# smartmp3.net
KiCad netlist of a schematic drawn in EasyEDA Pro
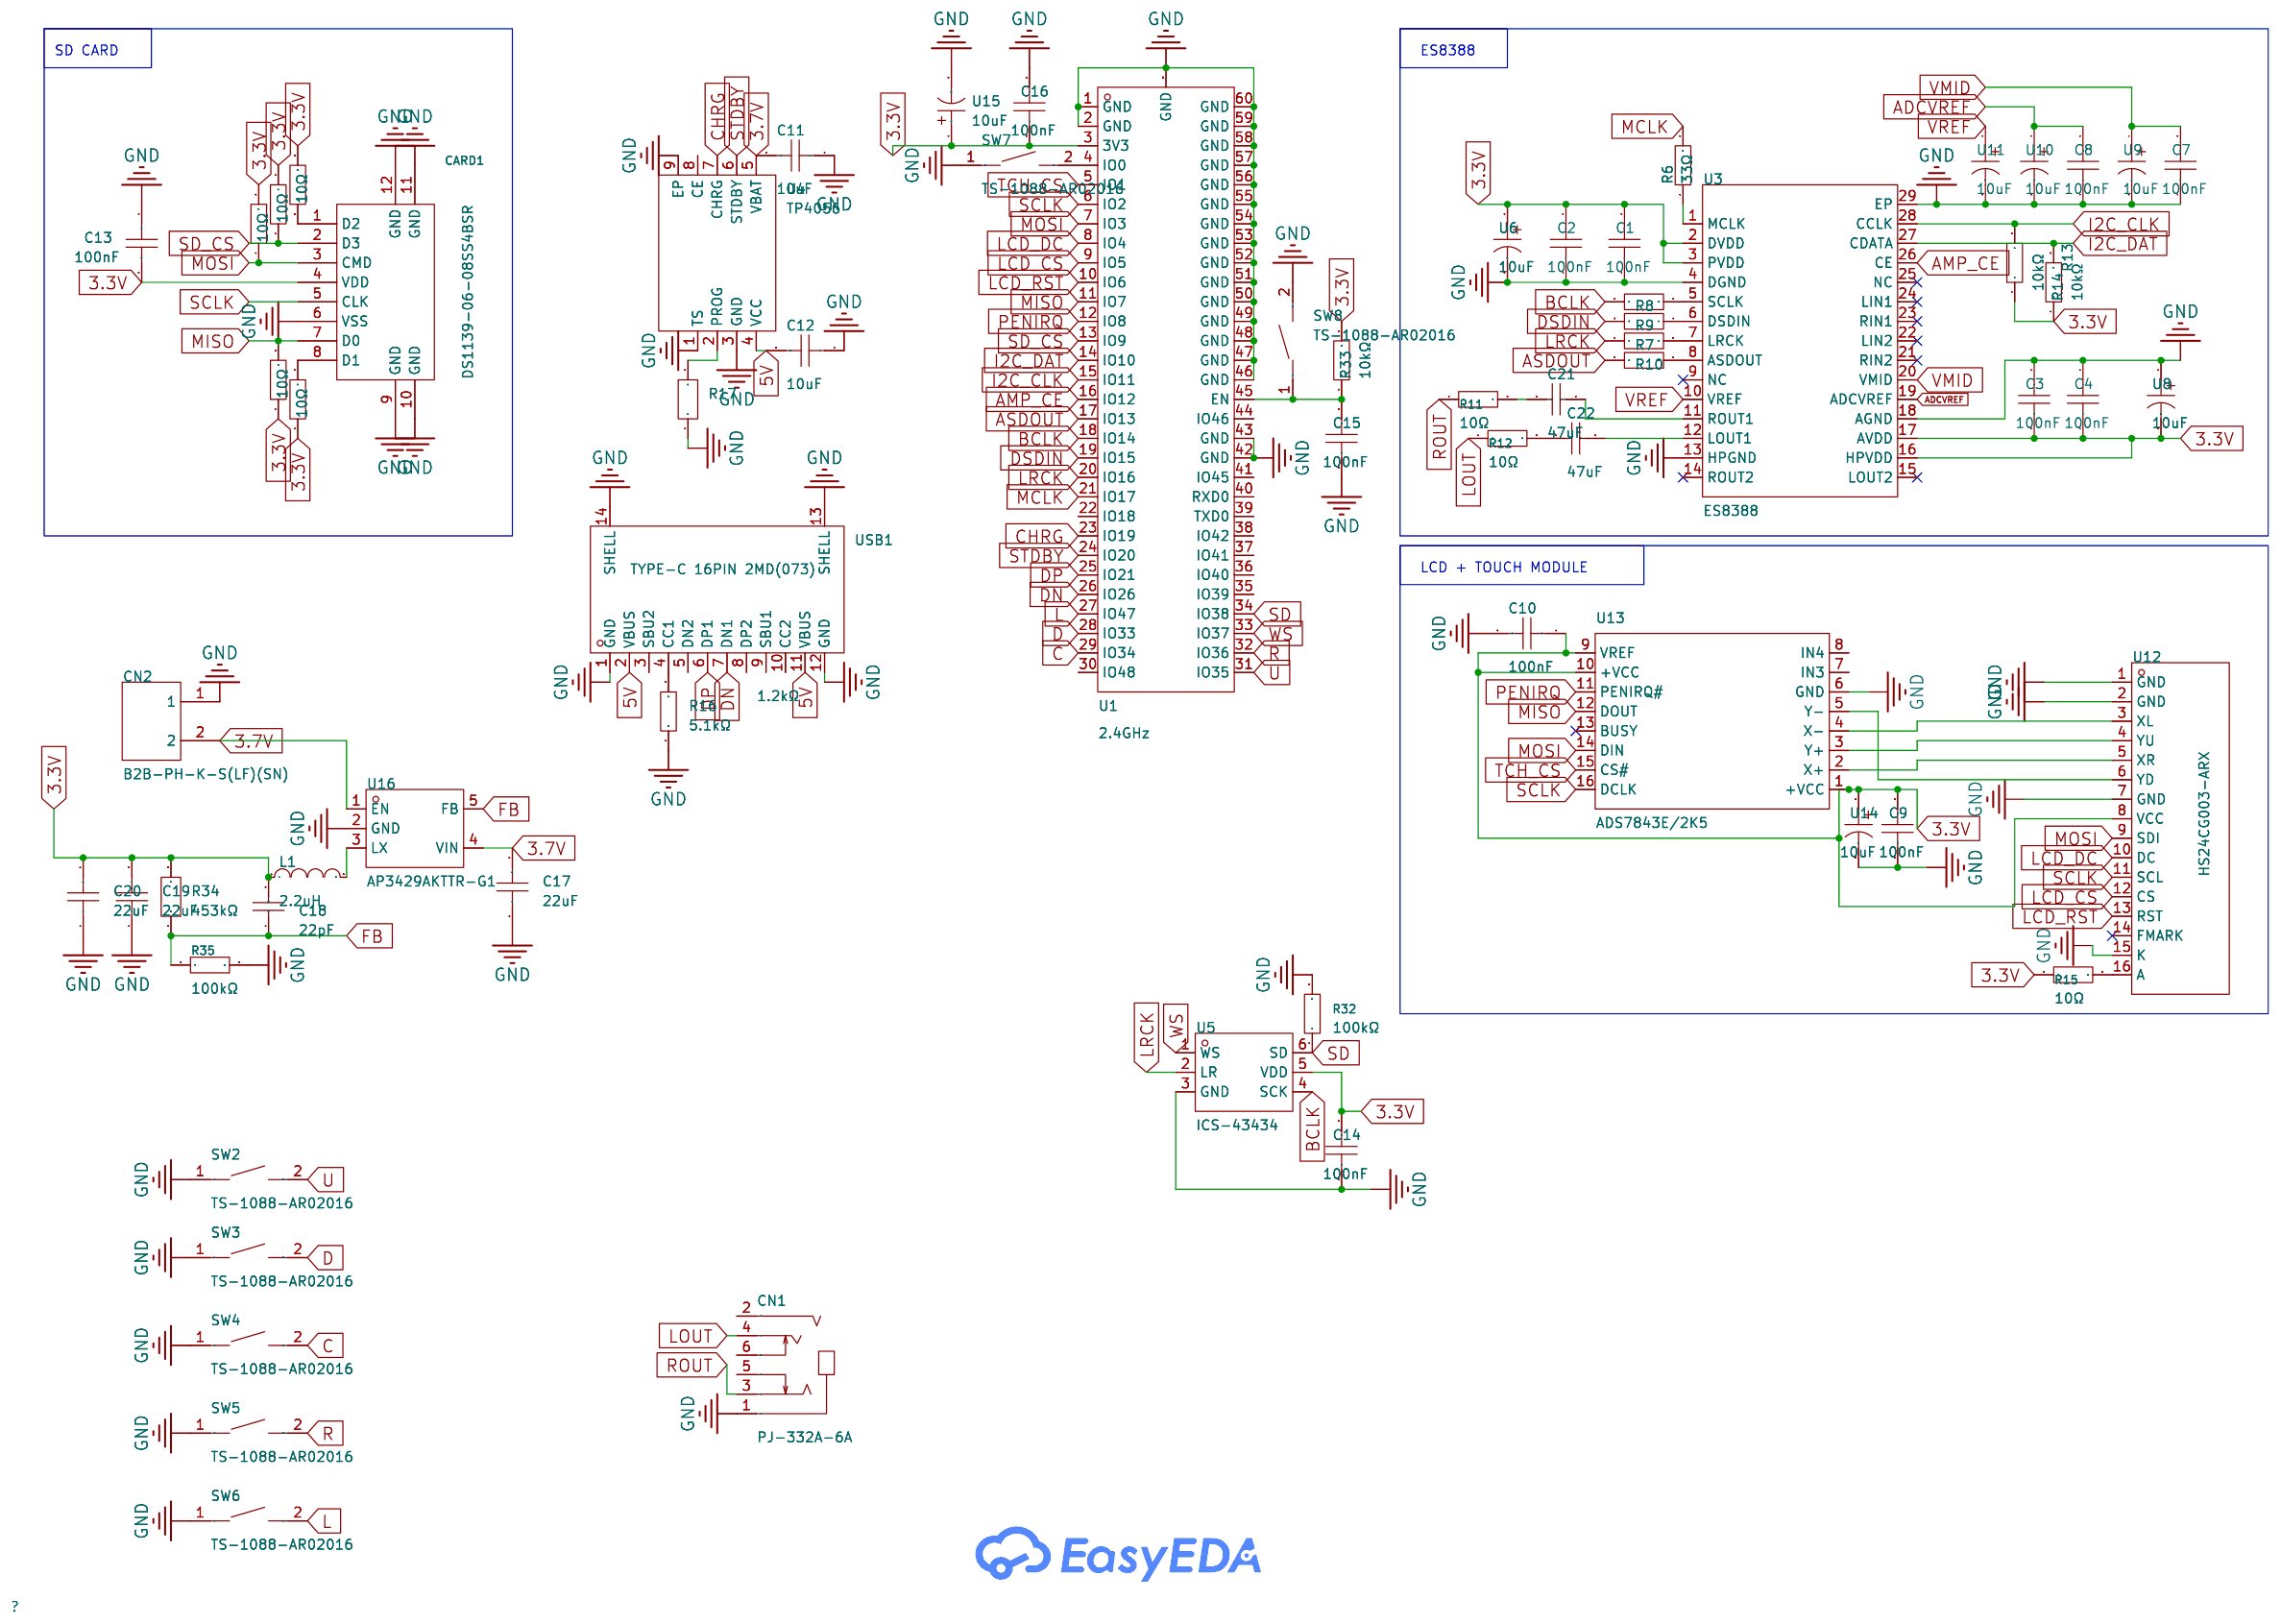
[diagram p0: schematic sheet]

(export (version "E")
  (design (tool "Eeschema 10.0.6"))
  (components
    (comp (ref "C1")
      (value "100nF")
      (footprint "easyedapro:C0402")
      (description "Capacitance:100nF Tolerance:±10% Tolerance:±10% Voltage Rating:16V Temperature Coefficient:-")
      (fields
        (field (name "Manufacturer Part") "CT41G-0402-2X1-16V-0.1μF-K(N)")
        (field (name "Manufacturer") "TORCH(火炬)")
      )
      (libsource (lib "easyedapro") (part "CT41G-0402-2X1-16V-0.1μF-K(N)"))
    )
    (comp (ref "C2")
      (value "100nF")
      (footprint "easyedapro:C0402")
      (description "Capacitance:100nF Tolerance:±10% Tolerance:±10% Voltage Rating:16V Temperature Coefficient:-")
      (fields
        (field (name "Manufacturer Part") "CT41G-0402-2X1-16V-0.1μF-K(N)")
        (field (name "Manufacturer") "TORCH(火炬)")
      )
      (libsource (lib "easyedapro") (part "CT41G-0402-2X1-16V-0.1μF-K(N)"))
    )
    (comp (ref "C3")
      (value "100nF")
      (footprint "easyedapro:C0402")
      (description "Capacitance:100nF Tolerance:±10% Tolerance:±10% Voltage Rating:16V Temperature Coefficient:-")
      (fields
        (field (name "Manufacturer Part") "CT41G-0402-2X1-16V-0.1μF-K(N)")
        (field (name "Manufacturer") "TORCH(火炬)")
      )
      (libsource (lib "easyedapro") (part "CT41G-0402-2X1-16V-0.1μF-K(N)"))
    )
    (comp (ref "C4")
      (value "100nF")
      (footprint "easyedapro:C0402")
      (description "Capacitance:100nF Tolerance:±10% Tolerance:±10% Voltage Rating:16V Temperature Coefficient:-")
      (fields
        (field (name "Manufacturer Part") "CT41G-0402-2X1-16V-0.1μF-K(N)")
        (field (name "Manufacturer") "TORCH(火炬)")
      )
      (libsource (lib "easyedapro") (part "CT41G-0402-2X1-16V-0.1μF-K(N)"))
    )
    (comp (ref "C7")
      (value "100nF")
      (footprint "easyedapro:C0402")
      (description "Capacitance:100nF Tolerance:±10% Tolerance:±10% Voltage Rating:16V Temperature Coefficient:-")
      (fields
        (field (name "Manufacturer Part") "CT41G-0402-2X1-16V-0.1μF-K(N)")
        (field (name "Manufacturer") "TORCH(火炬)")
      )
      (libsource (lib "easyedapro") (part "CT41G-0402-2X1-16V-0.1μF-K(N)"))
    )
    (comp (ref "C8")
      (value "100nF")
      (footprint "easyedapro:C0402")
      (description "Capacitance:100nF Tolerance:±10% Tolerance:±10% Voltage Rating:16V Temperature Coefficient:-")
      (fields
        (field (name "Manufacturer Part") "CT41G-0402-2X1-16V-0.1μF-K(N)")
        (field (name "Manufacturer") "TORCH(火炬)")
      )
      (libsource (lib "easyedapro") (part "CT41G-0402-2X1-16V-0.1μF-K(N)"))
    )
    (comp (ref "C9")
      (value "100nF")
      (footprint "easyedapro:C0402")
      (description "Capacitance:100nF Tolerance:±10% Tolerance:±10% Voltage Rating:16V Temperature Coefficient:-")
      (fields
        (field (name "Manufacturer Part") "CT41G-0402-2X1-16V-0.1μF-K(N)")
        (field (name "Manufacturer") "TORCH(火炬)")
      )
      (libsource (lib "easyedapro") (part "CT41G-0402-2X1-16V-0.1μF-K(N)"))
    )
    (comp (ref "C10")
      (value "100nF")
      (footprint "easyedapro:C0402")
      (description "Capacitance:100nF Tolerance:±10% Tolerance:±10% Voltage Rating:16V Temperature Coefficient:-")
      (fields
        (field (name "Manufacturer Part") "CT41G-0402-2X1-16V-0.1μF-K(N)")
        (field (name "Manufacturer") "TORCH(火炬)")
      )
      (libsource (lib "easyedapro") (part "CT41G-0402-2X1-16V-0.1μF-K(N)"))
    )
    (comp (ref "C11")
      (value "10uF")
      (footprint "easyedapro:C0805")
      (description "Capacitance:10uF Tolerance:±10% Tolerance:±10% Voltage Rating:25V Temperature Coefficient:X5R")
      (fields
        (field (name "Manufacturer Part") "CL21A106KAYNNNE")
        (field (name "Manufacturer") "SAMSUNG(三星)")
      )
      (libsource (lib "easyedapro") (part "CL21A106KAYNNNE"))
    )
    (comp (ref "C12")
      (value "10uF")
      (footprint "easyedapro:C0805")
      (description "Capacitance:10uF Tolerance:±10% Tolerance:±10% Voltage Rating:25V Temperature Coefficient:X5R")
      (fields
        (field (name "Manufacturer Part") "CL21A106KAYNNNE")
        (field (name "Manufacturer") "SAMSUNG(三星)")
      )
      (libsource (lib "easyedapro") (part "CL21A106KAYNNNE"))
    )
    (comp (ref "C13")
      (value "100nF")
      (footprint "easyedapro:C0402")
      (description "Capacitance:100nF Tolerance:±10% Tolerance:±10% Voltage Rating:16V Temperature Coefficient:-")
      (fields
        (field (name "Manufacturer Part") "CT41G-0402-2X1-16V-0.1μF-K(N)")
        (field (name "Manufacturer") "TORCH(火炬)")
      )
      (libsource (lib "easyedapro") (part "CT41G-0402-2X1-16V-0.1μF-K(N)"))
    )
    (comp (ref "C14")
      (value "100nF")
      (footprint "easyedapro:C0402")
      (description "Capacitance:100nF Tolerance:±10% Tolerance:±10% Voltage Rating:16V Temperature Coefficient:-")
      (fields
        (field (name "Manufacturer Part") "CT41G-0402-2X1-16V-0.1μF-K(N)")
        (field (name "Manufacturer") "TORCH(火炬)")
      )
      (libsource (lib "easyedapro") (part "CT41G-0402-2X1-16V-0.1μF-K(N)"))
    )
    (comp (ref "C15")
      (value "100nF")
      (footprint "easyedapro:C0402")
      (description "Capacitance:100nF Tolerance:±10% Tolerance:±10% Voltage Rating:16V Temperature Coefficient:-")
      (fields
        (field (name "Manufacturer Part") "CT41G-0402-2X1-16V-0.1μF-K(N)")
        (field (name "Manufacturer") "TORCH(火炬)")
      )
      (libsource (lib "easyedapro") (part "CT41G-0402-2X1-16V-0.1μF-K(N)"))
    )
    (comp (ref "C16")
      (value "100nF")
      (footprint "easyedapro:C0402")
      (description "Capacitance:100nF Tolerance:±10% Tolerance:±10% Voltage Rating:16V Temperature Coefficient:-")
      (fields
        (field (name "Manufacturer Part") "CT41G-0402-2X1-16V-0.1μF-K(N)")
        (field (name "Manufacturer") "TORCH(火炬)")
      )
      (libsource (lib "easyedapro") (part "CT41G-0402-2X1-16V-0.1μF-K(N)"))
    )
    (comp (ref "C17")
      (value "22uF")
      (footprint "easyedapro:C0805")
      (description "Capacitance:22uF Tolerance:±20% Tolerance:±20% Voltage Rating:25V Temperature Coefficient:X5R")
      (fields
        (field (name "Manufacturer Part") "CL21A226MAYNNNE")
        (field (name "Manufacturer") "SAMSUNG(三星)")
      )
      (libsource (lib "easyedapro") (part "CL21A226MAYNNNE"))
    )
    (comp (ref "C18")
      (value "22pF")
      (footprint "easyedapro:C0603")
      (description "Capacitance:22pF Tolerance:±5% Tolerance:±5% Voltage Rating:50V Temperature Coefficient:C0G")
      (fields
        (field (name "Manufacturer Part") "CL10C220JB8NNNC")
        (field (name "Manufacturer") "SAMSUNG(三星)")
      )
      (libsource (lib "easyedapro") (part "CL10C220JB8NNNC"))
    )
    (comp (ref "C19")
      (value "22uF")
      (footprint "easyedapro:C0805")
      (description "Capacitance:22uF Tolerance:±20% Tolerance:±20% Voltage Rating:25V Temperature Coefficient:X5R")
      (fields
        (field (name "Manufacturer Part") "CL21A226MAYNNNE")
        (field (name "Manufacturer") "SAMSUNG(三星)")
      )
      (libsource (lib "easyedapro") (part "CL21A226MAYNNNE"))
    )
    (comp (ref "C20")
      (value "22uF")
      (footprint "easyedapro:C0805")
      (description "Capacitance:22uF Tolerance:±20% Tolerance:±20% Voltage Rating:25V Temperature Coefficient:X5R")
      (fields
        (field (name "Manufacturer Part") "CL21A226MAYNNNE")
        (field (name "Manufacturer") "SAMSUNG(三星)")
      )
      (libsource (lib "easyedapro") (part "CL21A226MAYNNNE"))
    )
    (comp (ref "C21")
      (value "47uF")
      (footprint "easyedapro:C0805")
      (description "Capacitance:47uF Tolerance:±20% Tolerance:±20% Voltage Rating:6.3V Temperature Coefficient:X5R")
      (fields
        (field (name "Manufacturer Part") "CL21A476MQYNNNE")
        (field (name "Manufacturer") "SAMSUNG(三星)")
      )
      (libsource (lib "easyedapro") (part "CL21A476MQYNNNE"))
    )
    (comp (ref "C22")
      (value "47uF")
      (footprint "easyedapro:C0805")
      (description "Capacitance:47uF Tolerance:±20% Tolerance:±20% Voltage Rating:6.3V Temperature Coefficient:X5R")
      (fields
        (field (name "Manufacturer Part") "CL21A476MQYNNNE")
        (field (name "Manufacturer") "SAMSUNG(三星)")
      )
      (libsource (lib "easyedapro") (part "CL21A476MQYNNNE"))
    )
    (comp (ref "CARD1")
      (value "DS1139-06-08SS4BSR")
      (footprint "easyedapro:TF-SMD_DS1139-06-08SS4BSR")
      (fields (field (name "Manufacturer") "CONNFLY"))
      (libsource (lib "easyedapro") (part "DS1139-06-08SS4BSR"))
    )
    (comp (ref "CN1")
      (value "PJ-332A-6A")
      (footprint "easyedapro:AUDIO-SMD_PJ-332A-6A")
      (fields (field (name "Manufacturer") "韩国韩荣"))
      (libsource (lib "easyedapro") (part "PJ-332A-6A"))
    )
    (comp (ref "CN2")
      (value "B2B-PH-K-S(LF)(SN)")
      (footprint "easyedapro:CONN-TH_B2B-PH-K-S")
      (fields (field (name "Manufacturer") "JST"))
      (libsource (lib "easyedapro") (part "B2B-PH-K-S(LF)(SN)"))
    )
    (comp (ref "L1")
      (value "2.2uH")
      (footprint "easyedapro:L1008")
      (fields (field (name "Manufacturer Part") "LQM2HPN2R2MG0L") (field (name "Manufacturer") "muRata(村田)"))
      (libsource (lib "easyedapro") (part "LQM2HPN2R2MG0L"))
    )
    (comp (ref "R6")
      (value "33Ω")
      (footprint "easyedapro:R0402")
      (fields (field (name "Manufacturer Part") "RC0402FR-0733RL") (field (name "Manufacturer") "YAGEO(国巨)"))
      (libsource (lib "easyedapro") (part "RC0402FR-0733RL"))
    )
    (comp (ref "R7")
      (value "33Ω")
      (footprint "easyedapro:R0402")
      (fields (field (name "Manufacturer Part") "RC0402FR-0733RL") (field (name "Manufacturer") "YAGEO(国巨)"))
      (libsource (lib "easyedapro") (part "RC0402FR-0733RL"))
    )
    (comp (ref "R8")
      (value "33Ω")
      (footprint "easyedapro:R0402")
      (fields (field (name "Manufacturer Part") "RC0402FR-0733RL") (field (name "Manufacturer") "YAGEO(国巨)"))
      (libsource (lib "easyedapro") (part "RC0402FR-0733RL"))
    )
    (comp (ref "R9")
      (value "33Ω")
      (footprint "easyedapro:R0402")
      (fields (field (name "Manufacturer Part") "RC0402FR-0733RL") (field (name "Manufacturer") "YAGEO(国巨)"))
      (libsource (lib "easyedapro") (part "RC0402FR-0733RL"))
    )
    (comp (ref "R10")
      (value "33Ω")
      (footprint "easyedapro:R0402")
      (fields (field (name "Manufacturer Part") "RC0402FR-0733RL") (field (name "Manufacturer") "YAGEO(国巨)"))
      (libsource (lib "easyedapro") (part "RC0402FR-0733RL"))
    )
    (comp (ref "R11")
      (value "10Ω")
      (footprint "easyedapro:R0805_NEW")
      (fields
        (field (name "Manufacturer Part") "0805W8F100JT5E")
        (field (name "Manufacturer") "UNI-ROYAL(厚声)")
      )
      (libsource (lib "easyedapro") (part "0805W8F100JT5E"))
    )
    (comp (ref "R12")
      (value "10Ω")
      (footprint "easyedapro:R0805_NEW")
      (fields
        (field (name "Manufacturer Part") "0805W8F100JT5E")
        (field (name "Manufacturer") "UNI-ROYAL(厚声)")
      )
      (libsource (lib "easyedapro") (part "0805W8F100JT5E"))
    )
    (comp (ref "R13")
      (value "10kΩ")
      (footprint "easyedapro:R0603")
      (fields (field (name "Manufacturer Part") "RC0603FR-0710KL") (field (name "Manufacturer") "YAGEO(国巨)"))
      (libsource (lib "easyedapro") (part "RC0603FR-0710KL"))
    )
    (comp (ref "R14")
      (value "10kΩ")
      (footprint "easyedapro:R0603")
      (fields (field (name "Manufacturer Part") "RC0603FR-0710KL") (field (name "Manufacturer") "YAGEO(国巨)"))
      (libsource (lib "easyedapro") (part "RC0603FR-0710KL"))
    )
    (comp (ref "R15")
      (value "10Ω")
      (footprint "easyedapro:R0805_NEW")
      (fields
        (field (name "Manufacturer Part") "0805W8F100JT5E")
        (field (name "Manufacturer") "UNI-ROYAL(厚声)")
      )
      (libsource (lib "easyedapro") (part "0805W8F100JT5E"))
    )
    (comp (ref "R16")
      (value "5.1kΩ")
      (footprint "easyedapro:R0603")
      (fields (field (name "Manufacturer Part") "RC0603FR-075K1L") (field (name "Manufacturer") "YAGEO(国巨)"))
      (libsource (lib "easyedapro") (part "RC0603FR-075K1L"))
    )
    (comp (ref "R17")
      (value "1.2kΩ")
      (footprint "easyedapro:R1206")
      (fields (field (name "Manufacturer Part") "FRC1206J122 TS") (field (name "Manufacturer") "FOJAN(富捷)"))
      (libsource (lib "easyedapro") (part "FRC1206J122 TS"))
    )
    (comp (ref "R18")
      (value "10Ω")
      (footprint "easyedapro:R0805_NEW")
      (fields
        (field (name "Manufacturer Part") "0805W8F100JT5E")
        (field (name "Manufacturer") "UNI-ROYAL(厚声)")
      )
      (libsource (lib "easyedapro") (part "0805W8F100JT5E"))
    )
    (comp (ref "R19")
      (value "10Ω")
      (footprint "easyedapro:R0805_NEW")
      (fields
        (field (name "Manufacturer Part") "0805W8F100JT5E")
        (field (name "Manufacturer") "UNI-ROYAL(厚声)")
      )
      (libsource (lib "easyedapro") (part "0805W8F100JT5E"))
    )
    (comp (ref "R20")
      (value "10Ω")
      (footprint "easyedapro:R0805_NEW")
      (fields
        (field (name "Manufacturer Part") "0805W8F100JT5E")
        (field (name "Manufacturer") "UNI-ROYAL(厚声)")
      )
      (libsource (lib "easyedapro") (part "0805W8F100JT5E"))
    )
    (comp (ref "R22")
      (value "10Ω")
      (footprint "easyedapro:R0805_NEW")
      (fields
        (field (name "Manufacturer Part") "0805W8F100JT5E")
        (field (name "Manufacturer") "UNI-ROYAL(厚声)")
      )
      (libsource (lib "easyedapro") (part "0805W8F100JT5E"))
    )
    (comp (ref "R23")
      (value "10Ω")
      (footprint "easyedapro:R0805_NEW")
      (fields
        (field (name "Manufacturer Part") "0805W8F100JT5E")
        (field (name "Manufacturer") "UNI-ROYAL(厚声)")
      )
      (libsource (lib "easyedapro") (part "0805W8F100JT5E"))
    )
    (comp (ref "R32")
      (value "100kΩ")
      (footprint "easyedapro:R0603")
      (fields (field (name "Manufacturer Part") "RC0603FR-07100KL") (field (name "Manufacturer") "YAGEO(国巨)"))
      (libsource (lib "easyedapro") (part "RC0603FR-07100KL"))
    )
    (comp (ref "R33")
      (value "10kΩ")
      (footprint "easyedapro:R0603")
      (fields (field (name "Manufacturer Part") "RC0603FR-0710KL") (field (name "Manufacturer") "YAGEO(国巨)"))
      (libsource (lib "easyedapro") (part "RC0603FR-0710KL"))
    )
    (comp (ref "R34")
      (value "453kΩ")
      (footprint "easyedapro:R0603")
      (fields (field (name "Manufacturer Part") "FRC0603F4533TS") (field (name "Manufacturer") "FOJAN(富捷)"))
      (libsource (lib "easyedapro") (part "FRC0603F4533TS"))
    )
    (comp (ref "R35")
      (value "100kΩ")
      (footprint "easyedapro:R0603")
      (fields (field (name "Manufacturer Part") "RC0603FR-07100KL") (field (name "Manufacturer") "YAGEO(国巨)"))
      (libsource (lib "easyedapro") (part "RC0603FR-07100KL"))
    )
    (comp (ref "SW2")
      (value "TS-1088-AR02016")
      (footprint "easyedapro:SW-SMD_L3.9-W3.0-P4.45")
      (fields (field (name "Manufacturer") "XUNPU(讯普)"))
      (libsource (lib "easyedapro") (part "TS-1088-AR02016"))
    )
    (comp (ref "SW3")
      (value "TS-1088-AR02016")
      (footprint "easyedapro:SW-SMD_L3.9-W3.0-P4.45")
      (fields (field (name "Manufacturer") "XUNPU(讯普)"))
      (libsource (lib "easyedapro") (part "TS-1088-AR02016"))
    )
    (comp (ref "SW4")
      (value "TS-1088-AR02016")
      (footprint "easyedapro:SW-SMD_L3.9-W3.0-P4.45")
      (fields (field (name "Manufacturer") "XUNPU(讯普)"))
      (libsource (lib "easyedapro") (part "TS-1088-AR02016"))
    )
    (comp (ref "SW5")
      (value "TS-1088-AR02016")
      (footprint "easyedapro:SW-SMD_L3.9-W3.0-P4.45")
      (fields (field (name "Manufacturer") "XUNPU(讯普)"))
      (libsource (lib "easyedapro") (part "TS-1088-AR02016"))
    )
    (comp (ref "SW6")
      (value "TS-1088-AR02016")
      (footprint "easyedapro:SW-SMD_L3.9-W3.0-P4.45")
      (fields (field (name "Manufacturer") "XUNPU(讯普)"))
      (libsource (lib "easyedapro") (part "TS-1088-AR02016"))
    )
    (comp (ref "SW7")
      (value "TS-1088-AR02016")
      (footprint "easyedapro:SW-SMD_L3.9-W3.0-P4.45")
      (fields (field (name "Manufacturer") "XUNPU(讯普)"))
      (libsource (lib "easyedapro") (part "TS-1088-AR02016"))
    )
    (comp (ref "SW8")
      (value "TS-1088-AR02016")
      (footprint "easyedapro:SW-SMD_L3.9-W3.0-P4.45")
      (fields (field (name "Manufacturer") "XUNPU(讯普)"))
      (libsource (lib "easyedapro") (part "TS-1088-AR02016"))
    )
    (comp (ref "U1")
      (value "2.4GHz")
      (footprint "easyedapro:BULETM-SMD_ESP32-S3-MINI-1-N8")
      (fields
        (field (name "Manufacturer Part") "ESP32-S3-MINI-1-N8")
        (field (name "Manufacturer") "ESPRESSIF(乐鑫)")
      )
      (libsource (lib "easyedapro") (part "ESP32-S3-MINI-1-N8"))
    )
    (comp (ref "U3")
      (value "ES8388")
      (footprint "easyedapro:QFN-28_L4.0-W4.0-P0.45-BL-EP")
      (description "Voltage - Supply:1.7V~3.6V Voltage - Supply:1.7V~3.6V Interface Type:SPI；I2C")
      (fields (field (name "Manufacturer") "Everest-semi(顺芯)"))
      (libsource (lib "easyedapro") (part "ES8388"))
    )
    (comp (ref "U4")
      (value "TP4056")
      (footprint "easyedapro:ESOP-8_L4.9-W3.9-P1.27-LS6.0-BL-EP")
      (fields (field (name "Manufacturer") "JSMSEMI(杰盛微)"))
      (libsource (lib "easyedapro") (part "TP4056_C22470410"))
    )
    (comp (ref "U5")
      (value "ICS-43434")
      (footprint "easyedapro:MIC-SMD_6P-L3.5-W2.7-P0.90-BL")
      (fields (field (name "Manufacturer") "TDK InvenSense(应美盛)"))
      (libsource (lib "easyedapro") (part "ICS-43434_C5656610"))
    )
    (comp (ref "U6")
      (value "10uF")
      (footprint "easyedapro:CAP-SMD_BD4.0-L4.3-W4.3-LS5.0-FD")
      (fields (field (name "Manufacturer Part") "RST10UF35V015") (field (name "Manufacturer") "KNSCHA(科尼盛)"))
      (libsource (lib "easyedapro") (part "RST10UF35V015"))
    )
    (comp (ref "U8")
      (value "10uF")
      (footprint "easyedapro:CAP-SMD_BD4.0-L4.3-W4.3-LS5.0-FD")
      (fields (field (name "Manufacturer Part") "RST10UF35V015") (field (name "Manufacturer") "KNSCHA(科尼盛)"))
      (libsource (lib "easyedapro") (part "RST10UF35V015"))
    )
    (comp (ref "U9")
      (value "10uF")
      (footprint "easyedapro:CAP-SMD_BD4.0-L4.3-W4.3-LS5.0-FD")
      (fields (field (name "Manufacturer Part") "RST10UF35V015") (field (name "Manufacturer") "KNSCHA(科尼盛)"))
      (libsource (lib "easyedapro") (part "RST10UF35V015"))
    )
    (comp (ref "U10")
      (value "10uF")
      (footprint "easyedapro:CAP-SMD_BD4.0-L4.3-W4.3-LS5.0-FD")
      (fields (field (name "Manufacturer Part") "RST10UF35V015") (field (name "Manufacturer") "KNSCHA(科尼盛)"))
      (libsource (lib "easyedapro") (part "RST10UF35V015"))
    )
    (comp (ref "U11")
      (value "10uF")
      (footprint "easyedapro:CAP-SMD_BD4.0-L4.3-W4.3-LS5.0-FD")
      (fields (field (name "Manufacturer Part") "RST10UF35V015") (field (name "Manufacturer") "KNSCHA(科尼盛)"))
      (libsource (lib "easyedapro") (part "RST10UF35V015"))
    )
    (comp (ref "U12")
      (value "HS24CG003-ARX")
      (footprint "easyedapro:LCD-SMD_HS24CG003-ARX")
      (fields (field (name "Manufacturer") "HS(汉昇)"))
      (libsource (lib "easyedapro") (part "HS24CG003-ARX"))
    )
    (comp (ref "U13")
      (value "ADS7843E/2K5")
      (footprint "easyedapro:SSOP-16_L4.9-W3.9-P0.64-LS6.0-BL-1")
      (fields (field (name "Manufacturer") "TI(德州仪器)"))
      (libsource (lib "easyedapro") (part "ADS7843E/2K5"))
    )
    (comp (ref "U14")
      (value "10uF")
      (footprint "easyedapro:CAP-SMD_BD4.0-L4.3-W4.3-LS5.0-FD")
      (fields (field (name "Manufacturer Part") "RST10UF35V015") (field (name "Manufacturer") "KNSCHA(科尼盛)"))
      (libsource (lib "easyedapro") (part "RST10UF35V015"))
    )
    (comp (ref "U15")
      (value "10uF")
      (footprint "easyedapro:CAP-SMD_BD4.0-L4.3-W4.3-LS5.0-FD")
      (fields (field (name "Manufacturer Part") "RST10UF35V015") (field (name "Manufacturer") "KNSCHA(科尼盛)"))
      (libsource (lib "easyedapro") (part "RST10UF35V015"))
    )
    (comp (ref "U16")
      (value "AP3429AKTTR-G1")
      (footprint "easyedapro:TSOT-23-5_L2.9-W1.6-P0.95-LS2.8-BR")
      (fields (field (name "Manufacturer") "DIODES(美台)"))
      (libsource (lib "easyedapro") (part "AP3429AKTTR-G1"))
    )
    (comp (ref "USB1")
      (value "TYPE-C 16PIN 2MD(073)")
      (footprint "easyedapro:USB-C-SMD_TYPE-C-6PIN-2MD-073")
      (fields (field (name "Manufacturer") "SHOU HAN(首韩)"))
      (libsource (lib "easyedapro") (part "TYPE-C 16PIN 2MD(073)"))
    )
  )
  (nets
    (net (code "1") (name "3.3V") (class "Default")
      (node (ref "C1") (pin "2") (pinfunction "2_2") (pintype "unspecified"))
      (node (ref "C10") (pin "1") (pinfunction "1_1") (pintype "unspecified"))
      (node (ref "C13") (pin "2") (pinfunction "2_2") (pintype "unspecified"))
      (node (ref "C14") (pin "2") (pinfunction "2_2") (pintype "unspecified"))
      (node (ref "C16") (pin "1") (pinfunction "1_1") (pintype "unspecified"))
      (node (ref "C18") (pin "2") (pinfunction "2_2") (pintype "input"))
      (node (ref "C19") (pin "2") (pinfunction "2_2") (pintype "unspecified"))
      (node (ref "C2") (pin "2") (pinfunction "2_2") (pintype "unspecified"))
      (node (ref "C20") (pin "2") (pinfunction "2_2") (pintype "unspecified"))
      (node (ref "C3") (pin "1") (pinfunction "1_1") (pintype "unspecified"))
      (node (ref "C4") (pin "1") (pinfunction "1_1") (pintype "unspecified"))
      (node (ref "C9") (pin "2") (pinfunction "2_2") (pintype "unspecified"))
      (node (ref "CARD1") (pin "4") (pinfunction "VDD_4") (pintype "input"))
      (node (ref "L1") (pin "1") (pinfunction "1_1") (pintype "unspecified"))
      (node (ref "R13") (pin "1") (pinfunction "1_1") (pintype "input"))
      (node (ref "R14") (pin "1") (pinfunction "1_1") (pintype "input"))
      (node (ref "R15") (pin "1") (pinfunction "1_1") (pintype "input"))
      (node (ref "R18") (pin "2") (pinfunction "2_2") (pintype "input"))
      (node (ref "R19") (pin "2") (pinfunction "2_2") (pintype "input"))
      (node (ref "R20") (pin "2") (pinfunction "2_2") (pintype "input"))
      (node (ref "R22") (pin "1") (pinfunction "1_1") (pintype "input"))
      (node (ref "R23") (pin "1") (pinfunction "1_1") (pintype "input"))
      (node (ref "R33") (pin "2") (pinfunction "2_2") (pintype "input"))
      (node (ref "R34") (pin "2") (pinfunction "2_2") (pintype "unspecified"))
      (node (ref "U1") (pin "3") (pinfunction "3V3_3") (pintype "unspecified"))
      (node (ref "U12") (pin "8") (pinfunction "VCC_8") (pintype "unspecified"))
      (node (ref "U13") (pin "1") (pinfunction "+VCC_1") (pintype "unspecified"))
      (node (ref "U13") (pin "10") (pinfunction "+VCC_10") (pintype "unspecified"))
      (node (ref "U13") (pin "9") (pinfunction "VREF_9") (pintype "unspecified"))
      (node (ref "U14") (pin "1") (pinfunction "1_1") (pintype "input"))
      (node (ref "U15") (pin "1") (pinfunction "1_1") (pintype "input"))
      (node (ref "U3") (pin "16") (pinfunction "HPVDD_16") (pintype "unspecified"))
      (node (ref "U3") (pin "17") (pinfunction "AVDD_17") (pintype "unspecified"))
      (node (ref "U3") (pin "2") (pinfunction "DVDD_2") (pintype "unspecified"))
      (node (ref "U3") (pin "3") (pinfunction "PVDD_3") (pintype "unspecified"))
      (node (ref "U5") (pin "5") (pinfunction "VDD_5") (pintype "unspecified"))
      (node (ref "U6") (pin "1") (pinfunction "1_1") (pintype "input"))
      (node (ref "U8") (pin "2") (pinfunction "2_2") (pintype "input"))
    )
    (net (code "2") (name "3.7V") (class "Default")
      (node (ref "C11") (pin "2") (pinfunction "2_2") (pintype "unspecified"))
      (node (ref "C17") (pin "2") (pinfunction "2_2") (pintype "unspecified"))
      (node (ref "CN2") (pin "2") (pinfunction "2_2") (pintype "input"))
      (node (ref "U16") (pin "1") (pinfunction "EN_1") (pintype "unspecified"))
      (node (ref "U16") (pin "4") (pinfunction "VIN_4") (pintype "unspecified"))
      (node (ref "U4") (pin "5") (pinfunction "VBAT_5") (pintype "unspecified"))
    )
    (net (code "3") (name "5V") (class "Default")
      (node (ref "C12") (pin "2") (pinfunction "2_2") (pintype "unspecified"))
      (node (ref "U4") (pin "4") (pinfunction "VCC_4") (pintype "unspecified"))
      (node (ref "USB1") (pin "11") (pinfunction "VBUS_11") (pintype "unspecified"))
      (node (ref "USB1") (pin "2") (pinfunction "VBUS_2") (pintype "unspecified"))
    )
    (net (code "4") (name "ADCVREF") (class "Default")
      (node (ref "C8") (pin "2") (pinfunction "2_2") (pintype "unspecified"))
      (node (ref "U10") (pin "1") (pinfunction "1_1") (pintype "input"))
      (node (ref "U3") (pin "19") (pinfunction "ADCVREF_19") (pintype "unspecified"))
    )
    (net (code "5") (name "AMP_CE") (class "Default")
      (node (ref "U1") (pin "16") (pinfunction "IO12_16") (pintype "unspecified"))
      (node (ref "U3") (pin "26") (pinfunction "CE_26") (pintype "unspecified"))
    )
    (net (code "6") (name "ASDOUT") (class "Default")
      (node (ref "R10") (pin "2") (pinfunction "2_2") (pintype "input"))
      (node (ref "U1") (pin "17") (pinfunction "IO13_17") (pintype "unspecified"))
    )
    (net (code "7") (name "BCLK") (class "Default")
      (node (ref "R8") (pin "2") (pinfunction "2_2") (pintype "input"))
      (node (ref "U1") (pin "18") (pinfunction "IO14_18") (pintype "unspecified"))
      (node (ref "U5") (pin "4") (pinfunction "SCK_4") (pintype "unspecified"))
    )
    (net (code "8") (name "C") (class "Default")
      (node (ref "SW4") (pin "2") (pinfunction "2_2") (pintype "unspecified"))
      (node (ref "U1") (pin "29") (pinfunction "IO34_29") (pintype "unspecified"))
    )
    (net (code "9") (name "CHRG") (class "Default")
      (node (ref "U1") (pin "23") (pinfunction "IO19_23") (pintype "unspecified"))
      (node (ref "U4") (pin "7") (pinfunction "CHRG_7") (pintype "unspecified"))
    )
    (net (code "10") (name "D") (class "Default")
      (node (ref "SW3") (pin "2") (pinfunction "2_2") (pintype "unspecified"))
      (node (ref "U1") (pin "28") (pinfunction "IO33_28") (pintype "unspecified"))
    )
    (net (code "11") (name "DN") (class "Default")
      (node (ref "U1") (pin "26") (pinfunction "IO26_26") (pintype "unspecified"))
      (node (ref "USB1") (pin "7") (pinfunction "DN1_7") (pintype "unspecified"))
    )
    (net (code "12") (name "DP") (class "Default")
      (node (ref "U1") (pin "25") (pinfunction "IO21_25") (pintype "unspecified"))
      (node (ref "USB1") (pin "6") (pinfunction "DP1_6") (pintype "unspecified"))
    )
    (net (code "13") (name "DSDIN") (class "Default")
      (node (ref "R9") (pin "2") (pinfunction "2_2") (pintype "input"))
      (node (ref "U1") (pin "19") (pinfunction "IO15_19") (pintype "unspecified"))
    )
    (net (code "14") (name "FB") (class "Default")
      (node (ref "C18") (pin "1") (pinfunction "1_1") (pintype "input"))
      (node (ref "R34") (pin "1") (pinfunction "1_1") (pintype "unspecified"))
      (node (ref "R35") (pin "1") (pinfunction "1_1") (pintype "input"))
      (node (ref "U16") (pin "5") (pinfunction "FB_5") (pintype "unspecified"))
    )
    (net (code "15") (name "GND") (class "Default")
      (node (ref "C1") (pin "1") (pinfunction "1_1") (pintype "unspecified"))
      (node (ref "C10") (pin "2") (pinfunction "2_2") (pintype "unspecified"))
      (node (ref "C11") (pin "1") (pinfunction "1_1") (pintype "unspecified"))
      (node (ref "C12") (pin "1") (pinfunction "1_1") (pintype "unspecified"))
      (node (ref "C13") (pin "1") (pinfunction "1_1") (pintype "unspecified"))
      (node (ref "C14") (pin "1") (pinfunction "1_1") (pintype "unspecified"))
      (node (ref "C15") (pin "1") (pinfunction "1_1") (pintype "unspecified"))
      (node (ref "C16") (pin "2") (pinfunction "2_2") (pintype "unspecified"))
      (node (ref "C17") (pin "1") (pinfunction "1_1") (pintype "unspecified"))
      (node (ref "C19") (pin "1") (pinfunction "1_1") (pintype "unspecified"))
      (node (ref "C2") (pin "1") (pinfunction "1_1") (pintype "unspecified"))
      (node (ref "C20") (pin "1") (pinfunction "1_1") (pintype "unspecified"))
      (node (ref "C3") (pin "2") (pinfunction "2_2") (pintype "unspecified"))
      (node (ref "C4") (pin "2") (pinfunction "2_2") (pintype "unspecified"))
      (node (ref "C7") (pin "1") (pinfunction "1_1") (pintype "unspecified"))
      (node (ref "C8") (pin "1") (pinfunction "1_1") (pintype "unspecified"))
      (node (ref "C9") (pin "1") (pinfunction "1_1") (pintype "unspecified"))
      (node (ref "CARD1") (pin "10") (pinfunction "GND_10") (pintype "input"))
      (node (ref "CARD1") (pin "11") (pinfunction "GND_11") (pintype "input"))
      (node (ref "CARD1") (pin "12") (pinfunction "GND_12") (pintype "input"))
      (node (ref "CARD1") (pin "6") (pinfunction "VSS_6") (pintype "input"))
      (node (ref "CARD1") (pin "9") (pinfunction "GND_9") (pintype "input"))
      (node (ref "CN1") (pin "1") (pinfunction "1_1") (pintype "input"))
      (node (ref "CN2") (pin "1") (pinfunction "1_1") (pintype "input"))
      (node (ref "R16") (pin "1") (pinfunction "1_1") (pintype "input"))
      (node (ref "R17") (pin "1") (pinfunction "1_1") (pintype "unspecified"))
      (node (ref "R32") (pin "2") (pinfunction "2_2") (pintype "input"))
      (node (ref "R35") (pin "2") (pinfunction "2_2") (pintype "input"))
      (node (ref "SW2") (pin "1") (pinfunction "1_1") (pintype "unspecified"))
      (node (ref "SW3") (pin "1") (pinfunction "1_1") (pintype "unspecified"))
      (node (ref "SW4") (pin "1") (pinfunction "1_1") (pintype "unspecified"))
      (node (ref "SW5") (pin "1") (pinfunction "1_1") (pintype "unspecified"))
      (node (ref "SW6") (pin "1") (pinfunction "1_1") (pintype "unspecified"))
      (node (ref "SW7") (pin "1") (pinfunction "1_1") (pintype "unspecified"))
      (node (ref "SW8") (pin "2") (pinfunction "2_2") (pintype "unspecified"))
      (node (ref "U1") (pin "1") (pinfunction "GND_1") (pintype "unspecified"))
      (node (ref "U1") (pin "2") (pinfunction "GND_2") (pintype "unspecified"))
      (node (ref "U1") (pin "42") (pinfunction "GND_42") (pintype "unspecified"))
      (node (ref "U1") (pin "43") (pinfunction "GND_43") (pintype "unspecified"))
      (node (ref "U1") (pin "46") (pinfunction "GND_46") (pintype "unspecified"))
      (node (ref "U1") (pin "47") (pinfunction "GND_47") (pintype "unspecified"))
      (node (ref "U1") (pin "48") (pinfunction "GND_48") (pintype "unspecified"))
      (node (ref "U1") (pin "49") (pinfunction "GND_49") (pintype "unspecified"))
      (node (ref "U1") (pin "50") (pinfunction "GND_50") (pintype "unspecified"))
      (node (ref "U1") (pin "51") (pinfunction "GND_51") (pintype "unspecified"))
      (node (ref "U1") (pin "52") (pinfunction "GND_52") (pintype "unspecified"))
      (node (ref "U1") (pin "53") (pinfunction "GND_53") (pintype "unspecified"))
      (node (ref "U1") (pin "54") (pinfunction "GND_54") (pintype "unspecified"))
      (node (ref "U1") (pin "55") (pinfunction "GND_55") (pintype "unspecified"))
      (node (ref "U1") (pin "56") (pinfunction "GND_56") (pintype "unspecified"))
      (node (ref "U1") (pin "57") (pinfunction "GND_57") (pintype "unspecified"))
      (node (ref "U1") (pin "58") (pinfunction "GND_58") (pintype "unspecified"))
      (node (ref "U1") (pin "59") (pinfunction "GND_59") (pintype "unspecified"))
      (node (ref "U1") (pin "60") (pinfunction "GND_60") (pintype "unspecified"))
      (node (ref "U1") (pin "GND") (pinfunction "GND_GND") (pintype "unspecified"))
      (node (ref "U10") (pin "2") (pinfunction "2_2") (pintype "input"))
      (node (ref "U11") (pin "2") (pinfunction "2_2") (pintype "input"))
      (node (ref "U12") (pin "1") (pinfunction "GND_1") (pintype "unspecified"))
      (node (ref "U12") (pin "15") (pinfunction "K_15") (pintype "unspecified"))
      (node (ref "U12") (pin "2") (pinfunction "GND_2") (pintype "unspecified"))
      (node (ref "U12") (pin "7") (pinfunction "GND_7") (pintype "unspecified"))
      (node (ref "U13") (pin "6") (pinfunction "GND_6") (pintype "unspecified"))
      (node (ref "U14") (pin "2") (pinfunction "2_2") (pintype "input"))
      (node (ref "U15") (pin "2") (pinfunction "2_2") (pintype "input"))
      (node (ref "U16") (pin "2") (pinfunction "GND_2") (pintype "unspecified"))
      (node (ref "U3") (pin "13") (pinfunction "HPGND_13") (pintype "unspecified"))
      (node (ref "U3") (pin "18") (pinfunction "AGND_18") (pintype "unspecified"))
      (node (ref "U3") (pin "29") (pinfunction "EP_29") (pintype "unspecified"))
      (node (ref "U3") (pin "4") (pinfunction "DGND_4") (pintype "unspecified"))
      (node (ref "U4") (pin "1") (pinfunction "TS_1") (pintype "unspecified"))
      (node (ref "U4") (pin "3") (pinfunction "GND_3") (pintype "unspecified"))
      (node (ref "U4") (pin "9") (pinfunction "EP_9") (pintype "unspecified"))
      (node (ref "U5") (pin "3") (pinfunction "GND_3") (pintype "unspecified"))
      (node (ref "U6") (pin "2") (pinfunction "2_2") (pintype "input"))
      (node (ref "U8") (pin "1") (pinfunction "1_1") (pintype "input"))
      (node (ref "U9") (pin "2") (pinfunction "2_2") (pintype "input"))
      (node (ref "USB1") (pin "1") (pinfunction "GND_1") (pintype "unspecified"))
      (node (ref "USB1") (pin "12") (pinfunction "GND_12") (pintype "unspecified"))
      (node (ref "USB1") (pin "13") (pinfunction "SHELL_13") (pintype "unspecified"))
      (node (ref "USB1") (pin "14") (pinfunction "SHELL_14") (pintype "unspecified"))
    )
    (net (code "16") (name "I2C_CLK") (class "Default")
      (node (ref "R13") (pin "2") (pinfunction "2_2") (pintype "input"))
      (node (ref "U1") (pin "15") (pinfunction "IO11_15") (pintype "unspecified"))
      (node (ref "U3") (pin "28") (pinfunction "CCLK_28") (pintype "unspecified"))
    )
    (net (code "17") (name "I2C_DAT") (class "Default")
      (node (ref "R14") (pin "2") (pinfunction "2_2") (pintype "input"))
      (node (ref "U1") (pin "14") (pinfunction "IO10_14") (pintype "unspecified"))
      (node (ref "U3") (pin "27") (pinfunction "CDATA_27") (pintype "unspecified"))
    )
    (net (code "18") (name "L") (class "Default")
      (node (ref "SW6") (pin "2") (pinfunction "2_2") (pintype "unspecified"))
      (node (ref "U1") (pin "27") (pinfunction "IO47_27") (pintype "unspecified"))
    )
    (net (code "19") (name "LCD_CS") (class "Default")
      (node (ref "U1") (pin "9") (pinfunction "IO5_9") (pintype "unspecified"))
      (node (ref "U12") (pin "12") (pinfunction "CS_12") (pintype "unspecified"))
    )
    (net (code "20") (name "LCD_DC") (class "Default")
      (node (ref "U1") (pin "8") (pinfunction "IO4_8") (pintype "unspecified"))
      (node (ref "U12") (pin "10") (pinfunction "DC_10") (pintype "unspecified"))
    )
    (net (code "21") (name "LCD_RST") (class "Default")
      (node (ref "U1") (pin "10") (pinfunction "IO6_10") (pintype "unspecified"))
      (node (ref "U12") (pin "13") (pinfunction "RST_13") (pintype "unspecified"))
    )
    (net (code "22") (name "LOUT") (class "Default")
      (node (ref "CN1") (pin "4") (pinfunction "4_4") (pintype "input"))
      (node (ref "R12") (pin "1") (pinfunction "1_1") (pintype "input"))
    )
    (net (code "23") (name "LRCK") (class "Default")
      (node (ref "R7") (pin "1") (pinfunction "1_1") (pintype "input"))
      (node (ref "U1") (pin "20") (pinfunction "IO16_20") (pintype "unspecified"))
      (node (ref "U5") (pin "2") (pinfunction "LR_2") (pintype "unspecified"))
    )
    (net (code "24") (name "MCLK") (class "Default")
      (node (ref "R6") (pin "2") (pinfunction "2_2") (pintype "input"))
      (node (ref "U1") (pin "21") (pinfunction "IO17_21") (pintype "unspecified"))
    )
    (net (code "25") (name "MISO") (class "Default")
      (node (ref "CARD1") (pin "7") (pinfunction "D0_7") (pintype "input"))
      (node (ref "R22") (pin "2") (pinfunction "2_2") (pintype "input"))
      (node (ref "U1") (pin "11") (pinfunction "IO7_11") (pintype "unspecified"))
      (node (ref "U13") (pin "12") (pinfunction "DOUT_12") (pintype "unspecified"))
    )
    (net (code "26") (name "MOSI") (class "Default")
      (node (ref "CARD1") (pin "3") (pinfunction "CMD_3") (pintype "input"))
      (node (ref "R18") (pin "1") (pinfunction "1_1") (pintype "input"))
      (node (ref "U1") (pin "7") (pinfunction "IO3_7") (pintype "unspecified"))
      (node (ref "U12") (pin "9") (pinfunction "SDI_9") (pintype "unspecified"))
      (node (ref "U13") (pin "14") (pinfunction "DIN_14") (pintype "unspecified"))
    )
    (net (code "27") (name "Net-(C21-Pad1)") (class "Default")
      (node (ref "C21") (pin "1") (pinfunction "1_1") (pintype "input"))
      (node (ref "R11") (pin "2") (pinfunction "2_2") (pintype "input"))
    )
    (net (code "28") (name "Net-(C22-Pad1)") (class "Default")
      (node (ref "C22") (pin "1") (pinfunction "1_1") (pintype "input"))
      (node (ref "R12") (pin "2") (pinfunction "2_2") (pintype "input"))
    )
    (net (code "29") (name "Net-(CARD1-D1)") (class "Default")
      (node (ref "CARD1") (pin "8") (pinfunction "D1_8") (pintype "input"))
      (node (ref "R23") (pin "2") (pinfunction "2_2") (pintype "input"))
    )
    (net (code "30") (name "Net-(CARD1-D2)") (class "Default")
      (node (ref "CARD1") (pin "1") (pinfunction "D2_1") (pintype "input"))
      (node (ref "R20") (pin "1") (pinfunction "1_1") (pintype "input"))
    )
    (net (code "31") (name "Net-(U1-EN)") (class "Default")
      (node (ref "C15") (pin "2") (pinfunction "2_2") (pintype "unspecified"))
      (node (ref "R33") (pin "1") (pinfunction "1_1") (pintype "input"))
      (node (ref "SW8") (pin "1") (pinfunction "1_1") (pintype "unspecified"))
      (node (ref "U1") (pin "45") (pinfunction "EN_45") (pintype "unspecified"))
    )
    (net (code "32") (name "Net-(U1-IO0)") (class "Default")
      (node (ref "SW7") (pin "2") (pinfunction "2_2") (pintype "unspecified"))
      (node (ref "U1") (pin "4") (pinfunction "IO0_4") (pintype "unspecified"))
    )
    (net (code "33") (name "Net-(U3-ASDOUT)") (class "Default")
      (node (ref "R10") (pin "1") (pinfunction "1_1") (pintype "input"))
      (node (ref "U3") (pin "8") (pinfunction "ASDOUT_8") (pintype "unspecified"))
    )
    (net (code "34") (name "Net-(U3-DSDIN)") (class "Default")
      (node (ref "R9") (pin "1") (pinfunction "1_1") (pintype "input"))
      (node (ref "U3") (pin "6") (pinfunction "DSDIN_6") (pintype "unspecified"))
    )
    (net (code "35") (name "Net-(U3-LOUT1)") (class "Default")
      (node (ref "C22") (pin "2") (pinfunction "2_2") (pintype "input"))
      (node (ref "U3") (pin "12") (pinfunction "LOUT1_12") (pintype "unspecified"))
    )
    (net (code "36") (name "Net-(U3-LRCK)") (class "Default")
      (node (ref "R7") (pin "2") (pinfunction "2_2") (pintype "input"))
      (node (ref "U3") (pin "7") (pinfunction "LRCK_7") (pintype "unspecified"))
    )
    (net (code "37") (name "Net-(U3-MCLK)") (class "Default")
      (node (ref "R6") (pin "1") (pinfunction "1_1") (pintype "input"))
      (node (ref "U3") (pin "1") (pinfunction "MCLK_1") (pintype "unspecified"))
    )
    (net (code "38") (name "Net-(U3-ROUT1)") (class "Default")
      (node (ref "C21") (pin "2") (pinfunction "2_2") (pintype "input"))
      (node (ref "U3") (pin "11") (pinfunction "ROUT1_11") (pintype "unspecified"))
    )
    (net (code "39") (name "Net-(U3-SCLK)") (class "Default")
      (node (ref "R8") (pin "1") (pinfunction "1_1") (pintype "input"))
      (node (ref "U3") (pin "5") (pinfunction "SCLK_5") (pintype "unspecified"))
    )
    (net (code "40") (name "Net-(U4-PROG)") (class "Default")
      (node (ref "R17") (pin "2") (pinfunction "2_2") (pintype "unspecified"))
      (node (ref "U4") (pin "2") (pinfunction "PROG_2") (pintype "unspecified"))
    )
    (net (code "41") (name "Net-(U12-A)") (class "Default")
      (node (ref "R15") (pin "2") (pinfunction "2_2") (pintype "input"))
      (node (ref "U12") (pin "16") (pinfunction "A_16") (pintype "unspecified"))
    )
    (net (code "42") (name "Net-(U12-XL)") (class "Default")
      (node (ref "U12") (pin "3") (pinfunction "XL_3") (pintype "unspecified"))
      (node (ref "U13") (pin "4") (pinfunction "X-_4") (pintype "unspecified"))
    )
    (net (code "43") (name "Net-(U12-XR)") (class "Default")
      (node (ref "U12") (pin "5") (pinfunction "XR_5") (pintype "unspecified"))
      (node (ref "U13") (pin "2") (pinfunction "X+_2") (pintype "unspecified"))
    )
    (net (code "44") (name "Net-(U12-YD)") (class "Default")
      (node (ref "U12") (pin "6") (pinfunction "YD_6") (pintype "unspecified"))
      (node (ref "U13") (pin "5") (pinfunction "Y-_5") (pintype "unspecified"))
    )
    (net (code "45") (name "Net-(U12-YU)") (class "Default")
      (node (ref "U12") (pin "4") (pinfunction "YU_4") (pintype "unspecified"))
      (node (ref "U13") (pin "3") (pinfunction "Y+_3") (pintype "unspecified"))
    )
    (net (code "46") (name "Net-(U16-LX)") (class "Default")
      (node (ref "L1") (pin "2") (pinfunction "2_2") (pintype "unspecified"))
      (node (ref "U16") (pin "3") (pinfunction "LX_3") (pintype "unspecified"))
    )
    (net (code "47") (name "Net-(USB1-CC1)") (class "Default")
      (node (ref "R16") (pin "2") (pinfunction "2_2") (pintype "input"))
      (node (ref "USB1") (pin "4") (pinfunction "CC1_4") (pintype "unspecified"))
    )
    (net (code "48") (name "PENIRQ") (class "Default")
      (node (ref "U1") (pin "12") (pinfunction "IO8_12") (pintype "unspecified"))
      (node (ref "U13") (pin "11") (pinfunction "PENIRQ#_11") (pintype "unspecified"))
    )
    (net (code "49") (name "R") (class "Default")
      (node (ref "SW5") (pin "2") (pinfunction "2_2") (pintype "unspecified"))
      (node (ref "U1") (pin "32") (pinfunction "IO36_32") (pintype "unspecified"))
    )
    (net (code "50") (name "ROUT") (class "Default")
      (node (ref "CN1") (pin "3") (pinfunction "3_3") (pintype "input"))
      (node (ref "R11") (pin "1") (pinfunction "1_1") (pintype "input"))
    )
    (net (code "51") (name "SCLK") (class "Default")
      (node (ref "CARD1") (pin "5") (pinfunction "CLK_5") (pintype "input"))
      (node (ref "U1") (pin "6") (pinfunction "IO2_6") (pintype "unspecified"))
      (node (ref "U12") (pin "11") (pinfunction "SCL_11") (pintype "unspecified"))
      (node (ref "U13") (pin "16") (pinfunction "DCLK_16") (pintype "unspecified"))
    )
    (net (code "52") (name "SD") (class "Default")
      (node (ref "R32") (pin "1") (pinfunction "1_1") (pintype "input"))
      (node (ref "U1") (pin "34") (pinfunction "IO38_34") (pintype "unspecified"))
      (node (ref "U5") (pin "6") (pinfunction "SD_6") (pintype "unspecified"))
    )
    (net (code "53") (name "SD_CS") (class "Default")
      (node (ref "CARD1") (pin "2") (pinfunction "D3_2") (pintype "input"))
      (node (ref "R19") (pin "1") (pinfunction "1_1") (pintype "input"))
      (node (ref "U1") (pin "13") (pinfunction "IO9_13") (pintype "unspecified"))
    )
    (net (code "54") (name "STDBY") (class "Default")
      (node (ref "U1") (pin "24") (pinfunction "IO20_24") (pintype "unspecified"))
      (node (ref "U4") (pin "6") (pinfunction "STDBY_6") (pintype "unspecified"))
    )
    (net (code "55") (name "TCH_CS") (class "Default")
      (node (ref "U1") (pin "5") (pinfunction "IO1_5") (pintype "unspecified"))
      (node (ref "U13") (pin "15") (pinfunction "CS#_15") (pintype "unspecified"))
    )
    (net (code "56") (name "U") (class "Default")
      (node (ref "SW2") (pin "2") (pinfunction "2_2") (pintype "unspecified"))
      (node (ref "U1") (pin "31") (pinfunction "IO35_31") (pintype "unspecified"))
    )
    (net (code "57") (name "VMID") (class "Default")
      (node (ref "C7") (pin "2") (pinfunction "2_2") (pintype "unspecified"))
      (node (ref "U3") (pin "20") (pinfunction "VMID_20") (pintype "unspecified"))
      (node (ref "U9") (pin "1") (pinfunction "1_1") (pintype "input"))
    )
    (net (code "58") (name "VREF") (class "Default")
      (node (ref "U11") (pin "1") (pinfunction "1_1") (pintype "input"))
      (node (ref "U3") (pin "10") (pinfunction "VREF_10") (pintype "unspecified"))
    )
    (net (code "59") (name "WS") (class "Default")
      (node (ref "U1") (pin "33") (pinfunction "IO37_33") (pintype "unspecified"))
      (node (ref "U5") (pin "1") (pinfunction "WS_1") (pintype "unspecified"))
    )
    (net (code "60") (name "unconnected-(CN1-Pad2)") (class "Default")
      (node (ref "CN1") (pin "2") (pinfunction "2_2") (pintype "input"))
    )
    (net (code "61") (name "unconnected-(CN1-Pad5)") (class "Default")
      (node (ref "CN1") (pin "5") (pinfunction "5_5") (pintype "input"))
    )
    (net (code "62") (name "unconnected-(CN1-Pad6)") (class "Default")
      (node (ref "CN1") (pin "6") (pinfunction "6_6") (pintype "input"))
    )
    (net (code "63") (name "unconnected-(U1-IO18-Pad22)") (class "Default")
      (node (ref "U1") (pin "22") (pinfunction "IO18_22") (pintype "unspecified"))
    )
    (net (code "64") (name "unconnected-(U1-IO39-Pad35)") (class "Default")
      (node (ref "U1") (pin "35") (pinfunction "IO39_35") (pintype "unspecified"))
    )
    (net (code "65") (name "unconnected-(U1-IO40-Pad36)") (class "Default")
      (node (ref "U1") (pin "36") (pinfunction "IO40_36") (pintype "unspecified"))
    )
    (net (code "66") (name "unconnected-(U1-IO41-Pad37)") (class "Default")
      (node (ref "U1") (pin "37") (pinfunction "IO41_37") (pintype "unspecified"))
    )
    (net (code "67") (name "unconnected-(U1-IO42-Pad38)") (class "Default")
      (node (ref "U1") (pin "38") (pinfunction "IO42_38") (pintype "unspecified"))
    )
    (net (code "68") (name "unconnected-(U1-IO45-Pad41)") (class "Default")
      (node (ref "U1") (pin "41") (pinfunction "IO45_41") (pintype "unspecified"))
    )
    (net (code "69") (name "unconnected-(U1-IO46-Pad44)") (class "Default")
      (node (ref "U1") (pin "44") (pinfunction "IO46_44") (pintype "unspecified"))
    )
    (net (code "70") (name "unconnected-(U1-IO48-Pad30)") (class "Default")
      (node (ref "U1") (pin "30") (pinfunction "IO48_30") (pintype "unspecified"))
    )
    (net (code "71") (name "unconnected-(U1-RXD0-Pad40)") (class "Default")
      (node (ref "U1") (pin "40") (pinfunction "RXD0_40") (pintype "unspecified"))
    )
    (net (code "72") (name "unconnected-(U1-TXD0-Pad39)") (class "Default")
      (node (ref "U1") (pin "39") (pinfunction "TXD0_39") (pintype "unspecified"))
    )
    (net (code "73") (name "unconnected-(U3-LIN1-Pad24)") (class "Default")
      (node (ref "U3") (pin "24") (pinfunction "LIN1_24") (pintype "unspecified+no_connect"))
    )
    (net (code "74") (name "unconnected-(U3-LIN2-Pad22)") (class "Default")
      (node (ref "U3") (pin "22") (pinfunction "LIN2_22") (pintype "unspecified+no_connect"))
    )
    (net (code "75") (name "unconnected-(U3-LOUT2-Pad15)") (class "Default")
      (node (ref "U3") (pin "15") (pinfunction "LOUT2_15") (pintype "unspecified+no_connect"))
    )
    (net (code "76") (name "unconnected-(U3-NC-Pad9)") (class "Default")
      (node (ref "U3") (pin "9") (pinfunction "NC_9") (pintype "unspecified+no_connect"))
    )
    (net (code "77") (name "unconnected-(U3-NC-Pad25)") (class "Default")
      (node (ref "U3") (pin "25") (pinfunction "NC_25") (pintype "unspecified+no_connect"))
    )
    (net (code "78") (name "unconnected-(U3-RIN1-Pad23)") (class "Default")
      (node (ref "U3") (pin "23") (pinfunction "RIN1_23") (pintype "unspecified+no_connect"))
    )
    (net (code "79") (name "unconnected-(U3-RIN2-Pad21)") (class "Default")
      (node (ref "U3") (pin "21") (pinfunction "RIN2_21") (pintype "unspecified+no_connect"))
    )
    (net (code "80") (name "unconnected-(U3-ROUT2-Pad14)") (class "Default")
      (node (ref "U3") (pin "14") (pinfunction "ROUT2_14") (pintype "unspecified+no_connect"))
    )
    (net (code "81") (name "unconnected-(U4-CE-Pad8)") (class "Default")
      (node (ref "U4") (pin "8") (pinfunction "CE_8") (pintype "unspecified"))
    )
    (net (code "82") (name "unconnected-(U12-FMARK-Pad14)") (class "Default")
      (node (ref "U12") (pin "14") (pinfunction "FMARK_14") (pintype "unspecified+no_connect"))
    )
    (net (code "83") (name "unconnected-(U13-BUSY-Pad13)") (class "Default")
      (node (ref "U13") (pin "13") (pinfunction "BUSY_13") (pintype "unspecified+no_connect"))
    )
    (net (code "84") (name "unconnected-(U13-IN3-Pad7)") (class "Default")
      (node (ref "U13") (pin "7") (pinfunction "IN3_7") (pintype "unspecified"))
    )
    (net (code "85") (name "unconnected-(U13-IN4-Pad8)") (class "Default")
      (node (ref "U13") (pin "8") (pinfunction "IN4_8") (pintype "unspecified"))
    )
    (net (code "86") (name "unconnected-(USB1-CC2-Pad10)") (class "Default")
      (node (ref "USB1") (pin "10") (pinfunction "CC2_10") (pintype "unspecified"))
    )
    (net (code "87") (name "unconnected-(USB1-DN2-Pad5)") (class "Default")
      (node (ref "USB1") (pin "5") (pinfunction "DN2_5") (pintype "unspecified"))
    )
    (net (code "88") (name "unconnected-(USB1-DP2-Pad8)") (class "Default")
      (node (ref "USB1") (pin "8") (pinfunction "DP2_8") (pintype "unspecified"))
    )
    (net (code "89") (name "unconnected-(USB1-SBU1-Pad9)") (class "Default")
      (node (ref "USB1") (pin "9") (pinfunction "SBU1_9") (pintype "unspecified"))
    )
    (net (code "90") (name "unconnected-(USB1-SBU2-Pad3)") (class "Default")
      (node (ref "USB1") (pin "3") (pinfunction "SBU2_3") (pintype "unspecified"))
    )
  )
)
